# design.net
KiCad netlist of a schematic drawn in Altium Designer
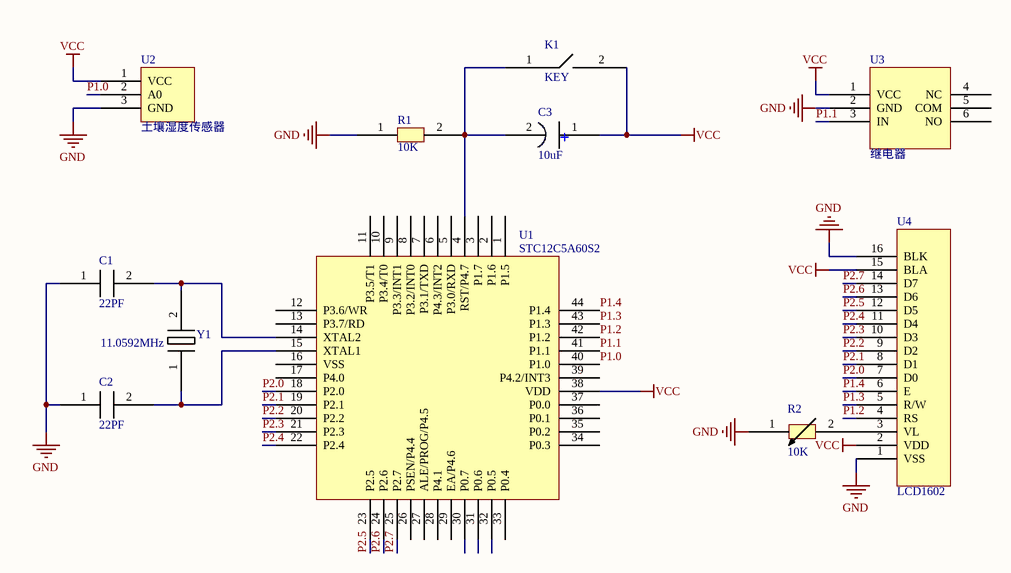
[diagram p0: 自动灌溉.SchDoc]

(export (version "E")
  (design (tool "Eeschema 10.0.6"))
  (components
    (comp (ref "C1") (value "22PF") (libsource (lib "Schlib1") (part "CAP")))
    (comp (ref "C2") (value "22PF") (libsource (lib "Schlib1") (part "CAP")))
    (comp (ref "C3") (value "10uF") (libsource (lib "Schlib1") (part "CAP2")))
    (comp (ref "K1") (value "KEY") (libsource (lib "Schlib1") (part "KEY")))
    (comp (ref "R1") (value "10K") (libsource (lib "Schlib1") (part "RES")))
    (comp (ref "R2") (value "10K") (libsource (lib "Schlib1") (part "滑动变阻器")))
    (comp (ref "U1") (value "STC12C5A60S2") (libsource (lib "Schlib1") (part "STC12C5A60S2")))
    (comp (ref "U2") (value "土壤湿度传感器") (libsource (lib "Schlib1") (part "土壤湿度传感器")))
    (comp (ref "U3") (value "继电器") (libsource (lib "Schlib1") (part "继电器")))
    (comp (ref "U4") (value "LCD1602") (libsource (lib "Schlib1") (part "LCD1602")))
    (comp (ref "Y1") (value "11.0592MHz") (libsource (lib "Schlib1") (part "晶振")))
  )
  (nets
    (net (code "1") (name "/P1.0") (class "Default")
      (node (ref "U1") (pin "40") (pinfunction "P1.0_40") (pintype "passive"))
      (node (ref "U2") (pin "2") (pinfunction "A0_2") (pintype "passive"))
    )
    (net (code "2") (name "/P1.1") (class "Default")
      (node (ref "U1") (pin "41") (pinfunction "P1.1_41") (pintype "passive"))
      (node (ref "U3") (pin "3") (pinfunction "IN_3") (pintype "passive"))
    )
    (net (code "3") (name "/P1.2") (class "Default")
      (node (ref "U1") (pin "42") (pinfunction "P1.2_42") (pintype "passive"))
      (node (ref "U4") (pin "4") (pinfunction "RS_4") (pintype "passive"))
    )
    (net (code "4") (name "/P1.3") (class "Default")
      (node (ref "U1") (pin "43") (pinfunction "P1.3_43") (pintype "passive"))
      (node (ref "U4") (pin "5") (pinfunction "R/W_5") (pintype "passive"))
    )
    (net (code "5") (name "/P1.4") (class "Default")
      (node (ref "U1") (pin "44") (pinfunction "P1.4_44") (pintype "passive"))
      (node (ref "U4") (pin "6") (pinfunction "E_6") (pintype "passive"))
    )
    (net (code "6") (name "/P2.0") (class "Default")
      (node (ref "U1") (pin "18") (pinfunction "P2.0_18") (pintype "passive"))
      (node (ref "U4") (pin "7") (pinfunction "D0_7") (pintype "passive"))
    )
    (net (code "7") (name "/P2.1") (class "Default")
      (node (ref "U1") (pin "19") (pinfunction "P2.1_19") (pintype "passive"))
      (node (ref "U4") (pin "8") (pinfunction "D1_8") (pintype "passive"))
    )
    (net (code "8") (name "/P2.2") (class "Default")
      (node (ref "U1") (pin "20") (pinfunction "P2.2_20") (pintype "passive"))
      (node (ref "U4") (pin "9") (pinfunction "D2_9") (pintype "passive"))
    )
    (net (code "9") (name "/P2.3") (class "Default")
      (node (ref "U1") (pin "21") (pinfunction "P2.3_21") (pintype "passive"))
      (node (ref "U4") (pin "10") (pinfunction "D3_10") (pintype "passive"))
    )
    (net (code "10") (name "/P2.4") (class "Default")
      (node (ref "U1") (pin "22") (pinfunction "P2.4_22") (pintype "passive"))
      (node (ref "U4") (pin "11") (pinfunction "D4_11") (pintype "passive"))
    )
    (net (code "11") (name "/P2.5") (class "Default")
      (node (ref "U1") (pin "23") (pinfunction "P2.5_23") (pintype "passive"))
      (node (ref "U4") (pin "12") (pinfunction "D5_12") (pintype "passive"))
    )
    (net (code "12") (name "/P2.6") (class "Default")
      (node (ref "U1") (pin "24") (pinfunction "P2.6_24") (pintype "passive"))
      (node (ref "U4") (pin "13") (pinfunction "D6_13") (pintype "passive"))
    )
    (net (code "13") (name "/P2.7") (class "Default")
      (node (ref "U1") (pin "25") (pinfunction "P2.7_25") (pintype "passive"))
      (node (ref "U4") (pin "14") (pinfunction "D7_14") (pintype "passive"))
    )
    (net (code "14") (name "GND") (class "Default")
      (node (ref "C1") (pin "1") (pintype "passive"))
      (node (ref "C2") (pin "1") (pintype "passive"))
      (node (ref "R1") (pin "1") (pintype "passive"))
      (node (ref "R2") (pin "1") (pintype "passive"))
      (node (ref "U2") (pin "3") (pinfunction "GND_3") (pintype "passive"))
      (node (ref "U3") (pin "2") (pinfunction "GND_2") (pintype "passive"))
      (node (ref "U4") (pin "1") (pinfunction "VSS_1") (pintype "passive"))
      (node (ref "U4") (pin "16") (pinfunction "BLK_16") (pintype "passive"))
    )
    (net (code "15") (name "Net-(U1-RST{slash}P4.7)") (class "Default")
      (node (ref "C3") (pin "2") (pintype "passive"))
      (node (ref "K1") (pin "1") (pintype "passive"))
      (node (ref "R1") (pin "2") (pintype "passive"))
      (node (ref "U1") (pin "4") (pinfunction "RST/P4.7_4") (pintype "passive"))
    )
    (net (code "16") (name "Net-(U1-XTAL1)") (class "Default")
      (node (ref "C2") (pin "2") (pintype "passive"))
      (node (ref "U1") (pin "15") (pinfunction "XTAL1_15") (pintype "passive"))
      (node (ref "Y1") (pin "1") (pintype "passive"))
    )
    (net (code "17") (name "Net-(U1-XTAL2)") (class "Default")
      (node (ref "C1") (pin "2") (pintype "passive"))
      (node (ref "U1") (pin "14") (pinfunction "XTAL2_14") (pintype "passive"))
      (node (ref "Y1") (pin "2") (pintype "passive"))
    )
    (net (code "18") (name "Net-(U4-VL)") (class "Default")
      (node (ref "R2") (pin "2") (pintype "passive"))
      (node (ref "U4") (pin "3") (pinfunction "VL_3") (pintype "passive"))
    )
    (net (code "19") (name "VCC") (class "Default")
      (node (ref "C3") (pin "1") (pintype "passive"))
      (node (ref "K1") (pin "2") (pintype "passive"))
      (node (ref "U1") (pin "38") (pinfunction "VDD_38") (pintype "passive"))
      (node (ref "U2") (pin "1") (pinfunction "VCC_1") (pintype "passive"))
      (node (ref "U3") (pin "1") (pinfunction "VCC_1") (pintype "passive"))
      (node (ref "U4") (pin "15") (pinfunction "BLA_15") (pintype "passive"))
      (node (ref "U4") (pin "2") (pinfunction "VDD_2") (pintype "passive"))
    )
    (net (code "20") (name "unconnected-(U1-ALE{slash}PROG{slash}P4.5-Pad27)") (class "Default")
      (node (ref "U1") (pin "27") (pinfunction "ALE/PROG/P4.5_27") (pintype "passive"))
    )
    (net (code "21") (name "unconnected-(U1-EA{slash}P4.6-Pad29)") (class "Default")
      (node (ref "U1") (pin "29") (pinfunction "EA/P4.6_29") (pintype "passive"))
    )
    (net (code "22") (name "unconnected-(U1-P0.0-Pad37)") (class "Default")
      (node (ref "U1") (pin "37") (pinfunction "P0.0_37") (pintype "passive"))
    )
    (net (code "23") (name "unconnected-(U1-P0.1-Pad36)") (class "Default")
      (node (ref "U1") (pin "36") (pinfunction "P0.1_36") (pintype "passive"))
    )
    (net (code "24") (name "unconnected-(U1-P0.2-Pad35)") (class "Default")
      (node (ref "U1") (pin "35") (pinfunction "P0.2_35") (pintype "passive"))
    )
    (net (code "25") (name "unconnected-(U1-P0.3-Pad34)") (class "Default")
      (node (ref "U1") (pin "34") (pinfunction "P0.3_34") (pintype "passive"))
    )
    (net (code "26") (name "unconnected-(U1-P0.4-Pad33)") (class "Default")
      (node (ref "U1") (pin "33") (pinfunction "P0.4_33") (pintype "passive"))
    )
    (net (code "27") (name "unconnected-(U1-P0.5-Pad32)") (class "Default")
      (node (ref "U1") (pin "32") (pinfunction "P0.5_32") (pintype "passive"))
    )
    (net (code "28") (name "unconnected-(U1-P0.6-Pad31)") (class "Default")
      (node (ref "U1") (pin "31") (pinfunction "P0.6_31") (pintype "passive"))
    )
    (net (code "29") (name "unconnected-(U1-P0.7-Pad30)") (class "Default")
      (node (ref "U1") (pin "30") (pinfunction "P0.7_30") (pintype "passive"))
    )
    (net (code "30") (name "unconnected-(U1-P1.5-Pad1)") (class "Default")
      (node (ref "U1") (pin "1") (pinfunction "P1.5_1") (pintype "passive"))
    )
    (net (code "31") (name "unconnected-(U1-P1.6-Pad2)") (class "Default")
      (node (ref "U1") (pin "2") (pinfunction "P1.6_2") (pintype "passive"))
    )
    (net (code "32") (name "unconnected-(U1-P1.7-Pad3)") (class "Default")
      (node (ref "U1") (pin "3") (pinfunction "P1.7_3") (pintype "passive"))
    )
    (net (code "33") (name "unconnected-(U1-P3.0{slash}RXD-Pad5)") (class "Default")
      (node (ref "U1") (pin "5") (pinfunction "P3.0/RXD_5") (pintype "passive"))
    )
    (net (code "34") (name "unconnected-(U1-P3.1{slash}TXD-Pad7)") (class "Default")
      (node (ref "U1") (pin "7") (pinfunction "P3.1/TXD_7") (pintype "passive"))
    )
    (net (code "35") (name "unconnected-(U1-P3.2{slash}INT0-Pad8)") (class "Default")
      (node (ref "U1") (pin "8") (pinfunction "P3.2/INT0_8") (pintype "passive"))
    )
    (net (code "36") (name "unconnected-(U1-P3.3{slash}INT1-Pad9)") (class "Default")
      (node (ref "U1") (pin "9") (pinfunction "P3.3/INT1_9") (pintype "passive"))
    )
    (net (code "37") (name "unconnected-(U1-P3.4{slash}T0-Pad10)") (class "Default")
      (node (ref "U1") (pin "10") (pinfunction "P3.4/T0_10") (pintype "passive"))
    )
    (net (code "38") (name "unconnected-(U1-P3.5{slash}T1-Pad11)") (class "Default")
      (node (ref "U1") (pin "11") (pinfunction "P3.5/T1_11") (pintype "passive"))
    )
    (net (code "39") (name "unconnected-(U1-P3.6{slash}WR-Pad12)") (class "Default")
      (node (ref "U1") (pin "12") (pinfunction "P3.6/WR_12") (pintype "passive"))
    )
    (net (code "40") (name "unconnected-(U1-P3.7{slash}RD-Pad13)") (class "Default")
      (node (ref "U1") (pin "13") (pinfunction "P3.7/RD_13") (pintype "passive"))
    )
    (net (code "41") (name "unconnected-(U1-P4.0-Pad17)") (class "Default")
      (node (ref "U1") (pin "17") (pinfunction "P4.0_17") (pintype "passive"))
    )
    (net (code "42") (name "unconnected-(U1-P4.1-Pad28)") (class "Default")
      (node (ref "U1") (pin "28") (pinfunction "P4.1_28") (pintype "passive"))
    )
    (net (code "43") (name "unconnected-(U1-P4.2{slash}INT3-Pad39)") (class "Default")
      (node (ref "U1") (pin "39") (pinfunction "P4.2/INT3_39") (pintype "passive"))
    )
    (net (code "44") (name "unconnected-(U1-P4.3{slash}INT2-Pad6)") (class "Default")
      (node (ref "U1") (pin "6") (pinfunction "P4.3/INT2_6") (pintype "passive"))
    )
    (net (code "45") (name "unconnected-(U1-PSEN{slash}P4.4-Pad26)") (class "Default")
      (node (ref "U1") (pin "26") (pinfunction "PSEN/P4.4_26") (pintype "passive"))
    )
    (net (code "46") (name "unconnected-(U1-VSS-Pad16)") (class "Default")
      (node (ref "U1") (pin "16") (pinfunction "VSS_16") (pintype "passive"))
    )
    (net (code "47") (name "unconnected-(U3-COM-Pad5)") (class "Default")
      (node (ref "U3") (pin "5") (pinfunction "COM_5") (pintype "passive"))
    )
    (net (code "48") (name "unconnected-(U3-NC-Pad4)") (class "Default")
      (node (ref "U3") (pin "4") (pinfunction "NC_4") (pintype "passive"))
    )
    (net (code "49") (name "unconnected-(U3-NO-Pad6)") (class "Default")
      (node (ref "U3") (pin "6") (pinfunction "NO_6") (pintype "passive"))
    )
  )
)
